# W501F.net
KiCad netlist of a schematic drawn in EAGLE
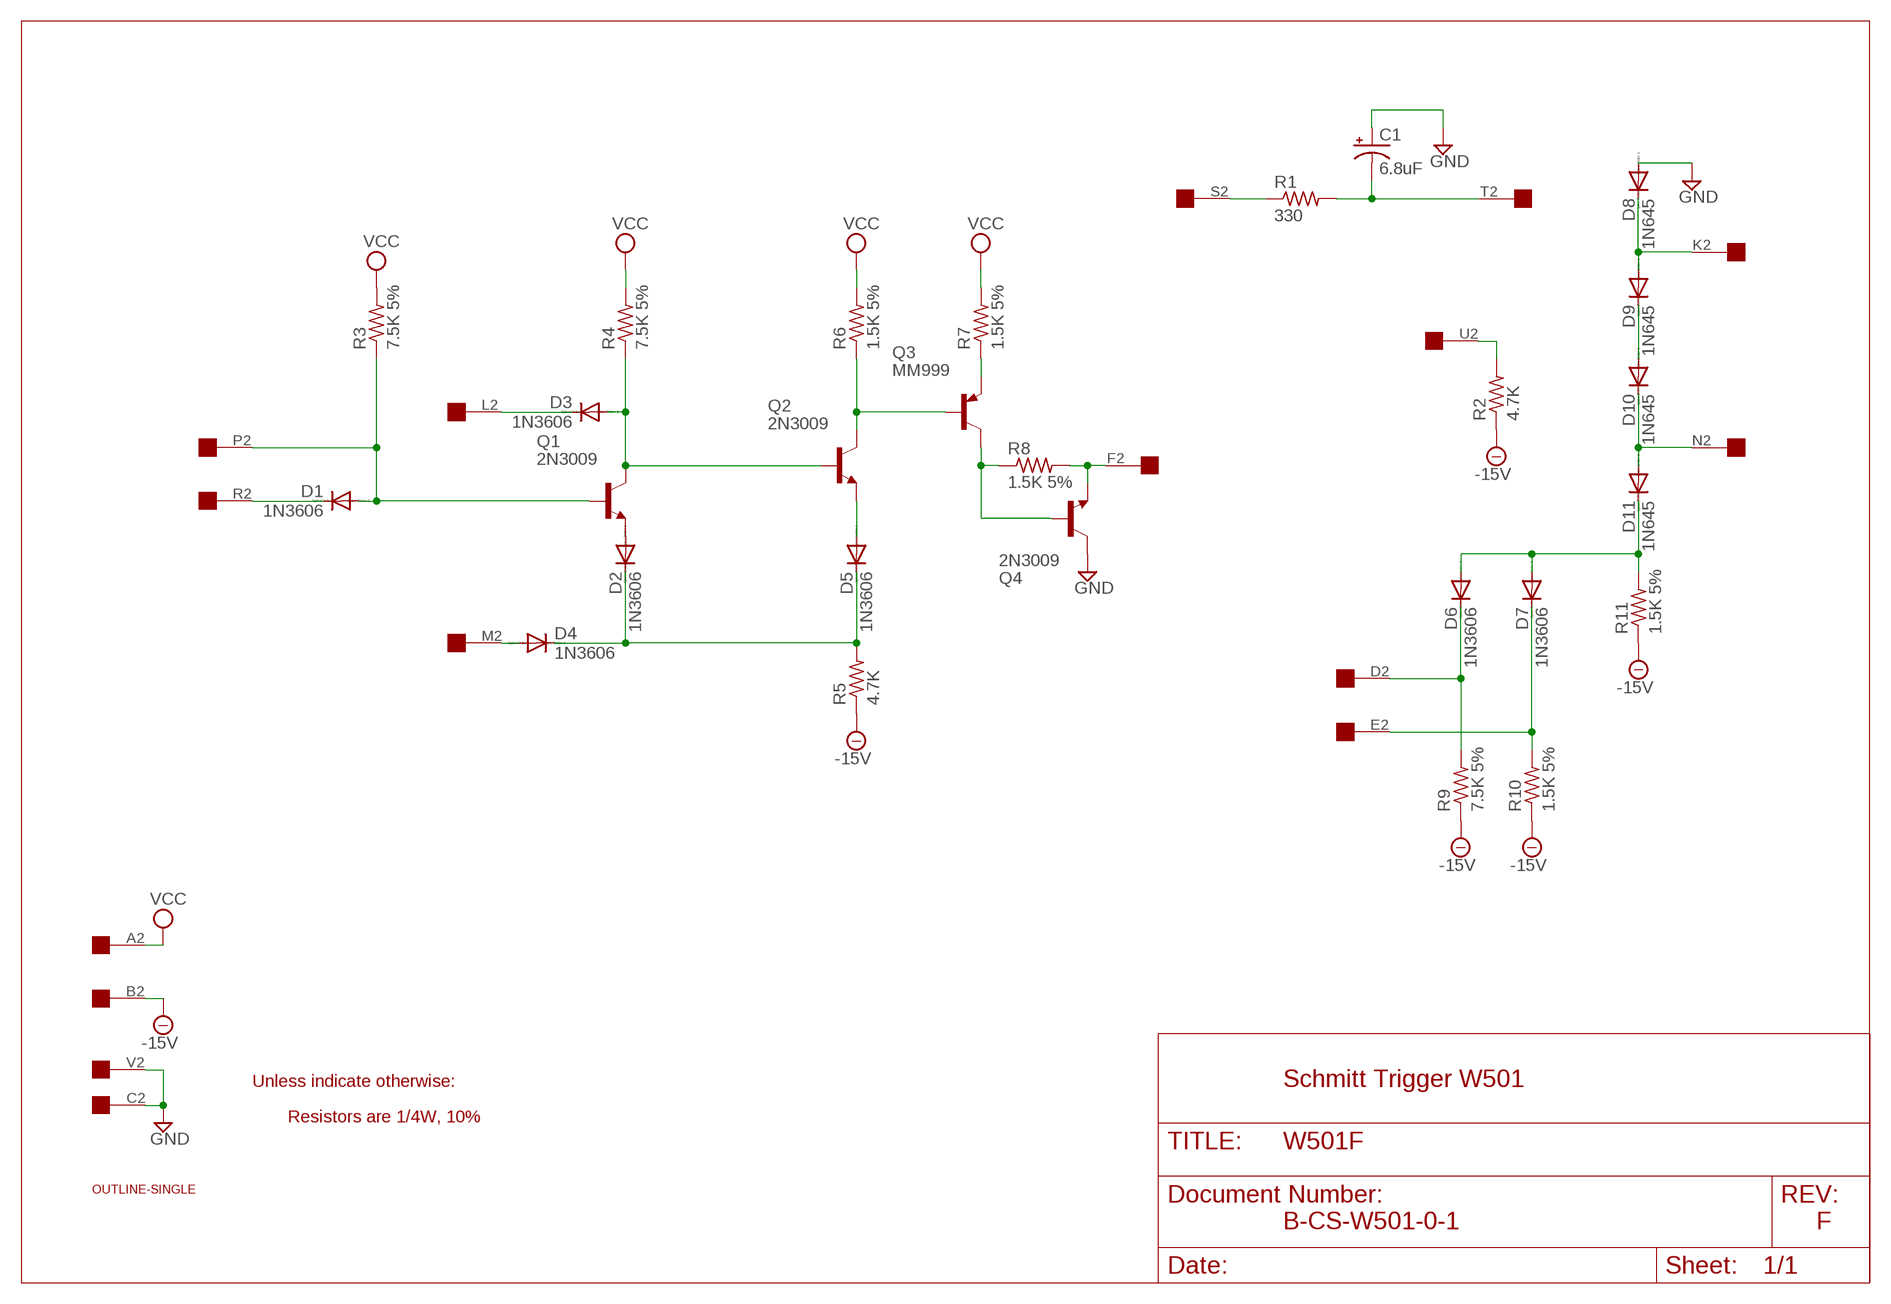
[diagram p0: schematic, sheet 1]

(export (version "E")
  (design (tool "Eeschema 10.0.6"))
  (components
    (comp (ref "C1")
      (value "6.8uF")
      (footprint "eagle-import:E15-5")
      (libsource (lib "eagle-import") (part "CPOL-USE15-5AXIAL"))
    )
    (comp (ref "D1")
      (value "1N3606")
      (footprint "eagle-import:DO35-10")
      (libsource (lib "eagle-import") (part "1N4148DO35-10"))
    )
    (comp (ref "D2")
      (value "1N3606")
      (footprint "eagle-import:DO35-10")
      (libsource (lib "eagle-import") (part "1N4148DO35-10"))
    )
    (comp (ref "D3")
      (value "1N3606")
      (footprint "eagle-import:DO35-10")
      (libsource (lib "eagle-import") (part "1N4148DO35-10"))
    )
    (comp (ref "D4")
      (value "1N3606")
      (footprint "eagle-import:DO35-10")
      (libsource (lib "eagle-import") (part "1N4148DO35-10"))
    )
    (comp (ref "D5")
      (value "1N3606")
      (footprint "eagle-import:DO35-10")
      (libsource (lib "eagle-import") (part "1N4148DO35-10"))
    )
    (comp (ref "D6")
      (value "1N3606")
      (footprint "eagle-import:DO35-10")
      (libsource (lib "eagle-import") (part "1N4148DO35-10"))
    )
    (comp (ref "D7")
      (value "1N3606")
      (footprint "eagle-import:DO35-10")
      (libsource (lib "eagle-import") (part "1N4148DO35-10"))
    )
    (comp (ref "D8")
      (value "1N645")
      (footprint "eagle-import:DO35-10")
      (libsource (lib "eagle-import") (part "1N4148DO35-10"))
    )
    (comp (ref "D9")
      (value "1N645")
      (footprint "eagle-import:DO35-10")
      (libsource (lib "eagle-import") (part "1N4148DO35-10"))
    )
    (comp (ref "D10")
      (value "1N645")
      (footprint "eagle-import:DO35-10")
      (libsource (lib "eagle-import") (part "1N4148DO35-10"))
    )
    (comp (ref "D11")
      (value "1N645")
      (footprint "eagle-import:DO35-10")
      (libsource (lib "eagle-import") (part "1N4148DO35-10"))
    )
    (comp (ref "EDGE")
      (value "EDGE-1")
      (footprint "eagle-import:EDGE-CON1")
      (libsource (lib "eagle-import") (part "EDGE-1"))
    )
    (comp (ref "Q1")
      (value "2N3009")
      (footprint "eagle-import:TO5")
      (libsource (lib "eagle-import") (part "2N2102"))
    )
    (comp (ref "Q2")
      (value "2N3009")
      (footprint "eagle-import:TO5")
      (libsource (lib "eagle-import") (part "2N2102"))
    )
    (comp (ref "Q3")
      (value "MM999")
      (footprint "eagle-import:TO39")
      (libsource (lib "eagle-import") (part "2N2904"))
    )
    (comp (ref "Q4")
      (value "2N3009")
      (footprint "eagle-import:TO5")
      (libsource (lib "eagle-import") (part "2N2102"))
    )
    (comp (ref "R1")
      (value "330")
      (footprint "eagle-import:0207_10")
      (libsource (lib "eagle-import") (part "R-US_0207/10"))
    )
    (comp (ref "R2")
      (value "4.7K")
      (footprint "eagle-import:0207_10")
      (libsource (lib "eagle-import") (part "R-US_0207/10"))
    )
    (comp (ref "R3")
      (value "7.5K 5%")
      (footprint "eagle-import:0207_10")
      (libsource (lib "eagle-import") (part "R-US_0207/10"))
    )
    (comp (ref "R4")
      (value "7.5K 5%")
      (footprint "eagle-import:0207_10")
      (libsource (lib "eagle-import") (part "R-US_0207/10"))
    )
    (comp (ref "R5")
      (value "4.7K")
      (footprint "eagle-import:0207_10")
      (libsource (lib "eagle-import") (part "R-US_0207/10"))
    )
    (comp (ref "R6")
      (value "1.5K 5%")
      (footprint "eagle-import:0207_10")
      (libsource (lib "eagle-import") (part "R-US_0207/10"))
    )
    (comp (ref "R7")
      (value "1.5K 5%")
      (footprint "eagle-import:0207_10")
      (libsource (lib "eagle-import") (part "R-US_0207/10"))
    )
    (comp (ref "R8")
      (value "1.5K 5%")
      (footprint "eagle-import:0207_10")
      (libsource (lib "eagle-import") (part "R-US_0207/10"))
    )
    (comp (ref "R9")
      (value "7.5K 5%")
      (footprint "eagle-import:0207_10")
      (libsource (lib "eagle-import") (part "R-US_0207/10"))
    )
    (comp (ref "R10")
      (value "1.5K 5%")
      (footprint "eagle-import:0207_10")
      (libsource (lib "eagle-import") (part "R-US_0207/10"))
    )
    (comp (ref "R11")
      (value "1.5K 5%")
      (footprint "eagle-import:0207_10")
      (libsource (lib "eagle-import") (part "R-US_0207/10"))
    )
    (comp (ref "U$1")
      (value "OUTLINE-SINGLE")
      (footprint "eagle-import:SINGLE")
      (libsource (lib "eagle-import") (part "OUTLINE-SINGLE"))
    )
  )
  (nets
    (net (code "1") (name "-15V") (class "Default")
      (node (ref "EDGE") (pin "B2") (pinfunction "1_B2") (pintype "bidirectional"))
      (node (ref "R10") (pin "1") (pinfunction "1_1") (pintype "passive"))
      (node (ref "R11") (pin "1") (pinfunction "1_1") (pintype "passive"))
      (node (ref "R2") (pin "1") (pinfunction "1_1") (pintype "passive"))
      (node (ref "R5") (pin "1") (pinfunction "1_1") (pintype "passive"))
      (node (ref "R9") (pin "1") (pinfunction "1_1") (pintype "passive"))
    )
    (net (code "2") (name "GND") (class "Default")
      (node (ref "C1") (pin "+") (pinfunction "+_+") (pintype "passive"))
      (node (ref "D8") (pin "A") (pinfunction "A_A") (pintype "passive"))
      (node (ref "EDGE") (pin "C2") (pinfunction "1_C2") (pintype "bidirectional"))
      (node (ref "EDGE") (pin "V2") (pinfunction "1_V2") (pintype "bidirectional"))
      (node (ref "Q4") (pin "3") (pinfunction "C_3") (pintype "passive"))
    )
    (net (code "3") (name "Net-(D2-PadC)") (class "Default")
      (node (ref "D2") (pin "C") (pinfunction "C_C") (pintype "passive"))
      (node (ref "D4") (pin "C") (pinfunction "C_C") (pintype "passive"))
      (node (ref "D5") (pin "C") (pinfunction "C_C") (pintype "passive"))
      (node (ref "R5") (pin "2") (pinfunction "2_2") (pintype "passive"))
    )
    (net (code "4") (name "Net-(D10-PadA)") (class "Default")
      (node (ref "D10") (pin "A") (pinfunction "A_A") (pintype "passive"))
      (node (ref "D9") (pin "C") (pinfunction "C_C") (pintype "passive"))
    )
    (net (code "5") (name "Net-(D11-PadC)") (class "Default")
      (node (ref "D11") (pin "C") (pinfunction "C_C") (pintype "passive"))
      (node (ref "D6") (pin "A") (pinfunction "A_A") (pintype "passive"))
      (node (ref "D7") (pin "A") (pinfunction "A_A") (pintype "passive"))
      (node (ref "R11") (pin "2") (pinfunction "2_2") (pintype "passive"))
    )
    (net (code "6") (name "Net-(EDGED-1)") (class "Default")
      (node (ref "D6") (pin "C") (pinfunction "C_C") (pintype "passive"))
      (node (ref "EDGE") (pin "D2") (pinfunction "1_D2") (pintype "bidirectional"))
      (node (ref "R9") (pin "2") (pinfunction "2_2") (pintype "passive"))
    )
    (net (code "7") (name "Net-(EDGEE-1)") (class "Default")
      (node (ref "D7") (pin "C") (pinfunction "C_C") (pintype "passive"))
      (node (ref "EDGE") (pin "E2") (pinfunction "1_E2") (pintype "bidirectional"))
      (node (ref "R10") (pin "2") (pinfunction "2_2") (pintype "passive"))
    )
    (net (code "8") (name "Net-(EDGEF-1)") (class "Default")
      (node (ref "EDGE") (pin "F2") (pinfunction "1_F2") (pintype "bidirectional"))
      (node (ref "Q4") (pin "1") (pinfunction "E_1") (pintype "passive"))
      (node (ref "R8") (pin "2") (pinfunction "2_2") (pintype "passive"))
    )
    (net (code "9") (name "Net-(EDGEI-1)") (class "Default")
      (node (ref "D8") (pin "C") (pinfunction "C_C") (pintype "passive"))
      (node (ref "D9") (pin "A") (pinfunction "A_A") (pintype "passive"))
      (node (ref "EDGE") (pin "K2") (pinfunction "1_K2") (pintype "bidirectional"))
    )
    (net (code "10") (name "Net-(EDGEJ-1)") (class "Default")
      (node (ref "D3") (pin "C") (pinfunction "C_C") (pintype "passive"))
      (node (ref "EDGE") (pin "L2") (pinfunction "1_L2") (pintype "bidirectional"))
    )
    (net (code "11") (name "Net-(EDGEK-1)") (class "Default")
      (node (ref "D4") (pin "A") (pinfunction "A_A") (pintype "passive"))
      (node (ref "EDGE") (pin "M2") (pinfunction "1_M2") (pintype "bidirectional"))
    )
    (net (code "12") (name "Net-(EDGEL-1)") (class "Default")
      (node (ref "D10") (pin "C") (pinfunction "C_C") (pintype "passive"))
      (node (ref "D11") (pin "A") (pinfunction "A_A") (pintype "passive"))
      (node (ref "EDGE") (pin "N2") (pinfunction "1_N2") (pintype "bidirectional"))
    )
    (net (code "13") (name "Net-(EDGEM-1)") (class "Default")
      (node (ref "D1") (pin "A") (pinfunction "A_A") (pintype "passive"))
      (node (ref "EDGE") (pin "P2") (pinfunction "1_P2") (pintype "bidirectional"))
      (node (ref "Q1") (pin "2") (pinfunction "B_2") (pintype "passive"))
      (node (ref "R3") (pin "1") (pinfunction "1_1") (pintype "passive"))
    )
    (net (code "14") (name "Net-(EDGEN-1)") (class "Default")
      (node (ref "D1") (pin "C") (pinfunction "C_C") (pintype "passive"))
      (node (ref "EDGE") (pin "R2") (pinfunction "1_R2") (pintype "bidirectional"))
    )
    (net (code "15") (name "Net-(EDGEO-1)") (class "Default")
      (node (ref "EDGE") (pin "S2") (pinfunction "1_S2") (pintype "bidirectional"))
      (node (ref "R1") (pin "1") (pinfunction "1_1") (pintype "passive"))
    )
    (net (code "16") (name "Net-(EDGEP-1)") (class "Default")
      (node (ref "C1") (pin "-") (pinfunction "-_-") (pintype "passive"))
      (node (ref "EDGE") (pin "T2") (pinfunction "1_T2") (pintype "bidirectional"))
      (node (ref "R1") (pin "2") (pinfunction "2_2") (pintype "passive"))
    )
    (net (code "17") (name "Net-(EDGEQ-1)") (class "Default")
      (node (ref "EDGE") (pin "U2") (pinfunction "1_U2") (pintype "bidirectional"))
      (node (ref "R2") (pin "2") (pinfunction "2_2") (pintype "passive"))
    )
    (net (code "18") (name "Net-(Q1-C)") (class "Default")
      (node (ref "D3") (pin "A") (pinfunction "A_A") (pintype "passive"))
      (node (ref "Q1") (pin "3") (pinfunction "C_3") (pintype "passive"))
      (node (ref "Q2") (pin "2") (pinfunction "B_2") (pintype "passive"))
      (node (ref "R4") (pin "1") (pinfunction "1_1") (pintype "passive"))
    )
    (net (code "19") (name "Net-(Q1-E)") (class "Default")
      (node (ref "D2") (pin "A") (pinfunction "A_A") (pintype "passive"))
      (node (ref "Q1") (pin "1") (pinfunction "E_1") (pintype "passive"))
    )
    (net (code "20") (name "Net-(Q2-C)") (class "Default")
      (node (ref "Q2") (pin "3") (pinfunction "C_3") (pintype "passive"))
      (node (ref "Q3") (pin "2") (pinfunction "B_2") (pintype "passive"))
      (node (ref "R6") (pin "1") (pinfunction "1_1") (pintype "passive"))
    )
    (net (code "21") (name "Net-(Q2-E)") (class "Default")
      (node (ref "D5") (pin "A") (pinfunction "A_A") (pintype "passive"))
      (node (ref "Q2") (pin "1") (pinfunction "E_1") (pintype "passive"))
    )
    (net (code "22") (name "Net-(Q3-C)") (class "Default")
      (node (ref "Q3") (pin "3") (pinfunction "C_3") (pintype "passive"))
      (node (ref "Q4") (pin "2") (pinfunction "B_2") (pintype "passive"))
      (node (ref "R8") (pin "1") (pinfunction "1_1") (pintype "passive"))
    )
    (net (code "23") (name "Net-(Q3-E)") (class "Default")
      (node (ref "Q3") (pin "1") (pinfunction "E_1") (pintype "passive"))
      (node (ref "R7") (pin "1") (pinfunction "1_1") (pintype "passive"))
    )
    (net (code "24") (name "VCC") (class "Default")
      (node (ref "EDGE") (pin "A2") (pinfunction "1_A2") (pintype "bidirectional"))
      (node (ref "R3") (pin "2") (pinfunction "2_2") (pintype "passive"))
      (node (ref "R4") (pin "2") (pinfunction "2_2") (pintype "passive"))
      (node (ref "R6") (pin "2") (pinfunction "2_2") (pintype "passive"))
      (node (ref "R7") (pin "2") (pinfunction "2_2") (pintype "passive"))
    )
  )
)
